# button_fingers.net
KiCad netlist of a schematic drawn in EAGLE
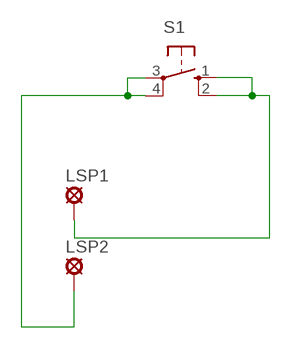
[diagram p0: schematic, sheet 1]

(export (version "E")
  (design (tool "Eeschema 10.0.6"))
  (components
    (comp (ref "LSP1")
      (value "SE14")
      (footprint "eagle-import:SE14")
      (libsource (lib "eagle-import") (part "SE14"))
    )
    (comp (ref "LSP2")
      (value "SE14")
      (footprint "eagle-import:SE14")
      (libsource (lib "eagle-import") (part "SE14"))
    )
    (comp (ref "S1")
      (value "10-XX")
      (footprint "eagle-import:B3F-10XX")
      (fields (field (name "MPN") "B3F-1000"))
      (libsource (lib "eagle-import") (part "10-XX"))
    )
  )
  (nets
    (net (code "1") (name "Net-(S1-P)") (class "Default")
      (node (ref "LSP2") (pin "MP") (pinfunction "MP_MP") (pintype "passive"))
      (node (ref "S1") (pin "3") (pinfunction "P_3") (pintype "passive"))
      (node (ref "S1") (pin "4") (pinfunction "P1_4") (pintype "passive"))
    )
    (net (code "2") (name "Net-(S1-S)") (class "Default")
      (node (ref "LSP1") (pin "MP") (pinfunction "MP_MP") (pintype "passive"))
      (node (ref "S1") (pin "1") (pinfunction "S_1") (pintype "passive"))
      (node (ref "S1") (pin "2") (pinfunction "S1_2") (pintype "passive"))
    )
  )
)
